# design.net
KiCad netlist of a schematic drawn in Altium Designer
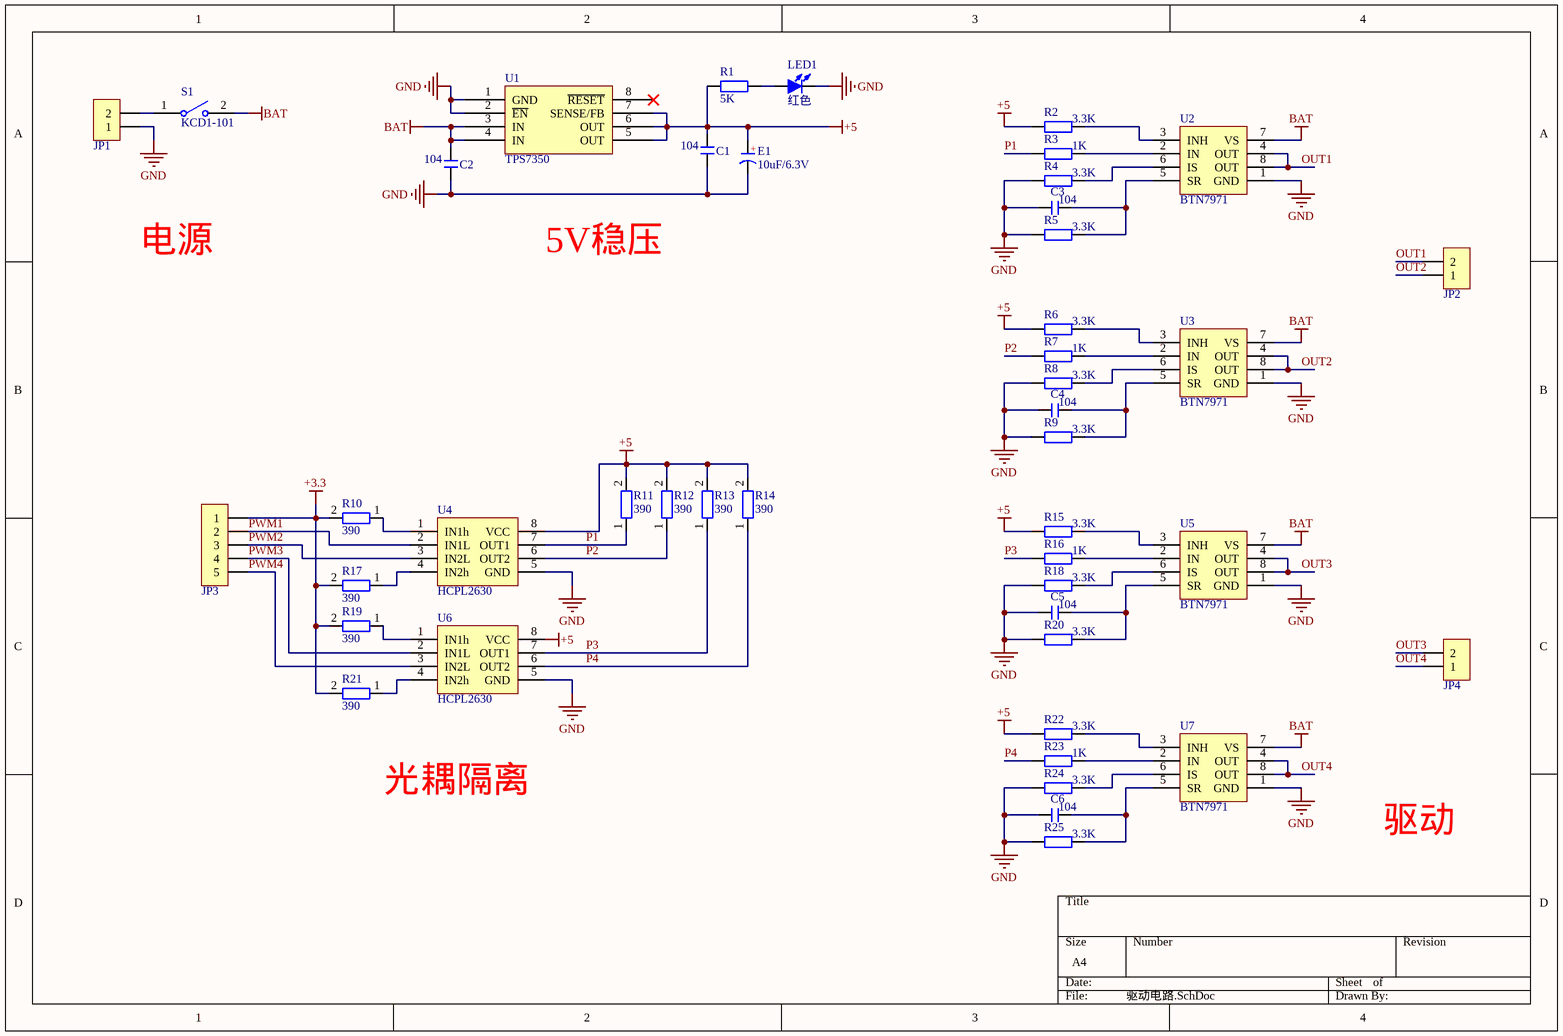
[diagram p0: 驱动电路.SchDoc]

(export (version "E")
  (design (tool "Eeschema 10.0.6"))
  (components
    (comp (ref "C1")
      (value "104")
      (footprint "C 0805_M")
      (description "无极性贴片电容")
      (fields (field (name "版权归属") "源创客"))
      (libsource (lib "3.1   - 电阻-电容-电感") (part "C"))
    )
    (comp (ref "C2")
      (value "104")
      (footprint "C 0805_M")
      (description "无极性贴片电容")
      (fields (field (name "版权归属") "源创客"))
      (libsource (lib "3.1   - 电阻-电容-电感") (part "C"))
    )
    (comp (ref "C3")
      (value "104")
      (footprint "C 0805_M")
      (description "无极性贴片电容")
      (fields (field (name "版权归属") "源创客"))
      (libsource (lib "3.1   - 电阻-电容-电感") (part "C"))
    )
    (comp (ref "C4")
      (value "104")
      (footprint "C 0805_M")
      (description "无极性贴片电容")
      (fields (field (name "版权归属") "源创客"))
      (libsource (lib "3.1   - 电阻-电容-电感") (part "C"))
    )
    (comp (ref "C5")
      (value "104")
      (footprint "C 0805_M")
      (description "无极性贴片电容")
      (fields (field (name "版权归属") "源创客"))
      (libsource (lib "3.1   - 电阻-电容-电感") (part "C"))
    )
    (comp (ref "C6")
      (value "104")
      (footprint "C 0805_M")
      (description "无极性贴片电容")
      (fields (field (name "版权归属") "源创客"))
      (libsource (lib "3.1   - 电阻-电容-电感") (part "C"))
    )
    (comp (ref "E1")
      (value "10uF/6.3V")
      (footprint "CD A(3216)")
      (description "贴片钽电容")
      (fields (field (name "版权归属") "源创客"))
      (libsource (lib "3.1   - 电阻-电容-电感") (part "C-CD"))
    )
    (comp (ref "JP1")
      (value "HDR-1X2")
      (footprint "KF128-5.08-2P")
      (description "2P接插件")
      (fields (field (name "版权归属") "源创客"))
      (libsource (lib "") (part "Header 2_1"))
    )
    (comp (ref "JP2")
      (value "HDR-1X2")
      (footprint "KF128-5.08-2P")
      (description "2P接插件")
      (fields (field (name "版权归属") "源创客"))
      (libsource (lib "4.10 - 接插件-脚距5.08") (part "Header 2"))
    )
    (comp (ref "JP3")
      (value "HDR-1X5")
      (footprint "XH2.54-LI-5P")
      (description "5P接插件")
      (fields (field (name "版权归属") "源创客"))
      (libsource (lib "4.5   - 接插件-脚距2.54") (part "Header 5"))
    )
    (comp (ref "JP4")
      (value "HDR-1X2")
      (footprint "KF128-5.08-2P")
      (description "2P接插件")
      (fields (field (name "版权归属") "源创客"))
      (libsource (lib "4.10 - 接插件-脚距5.08") (part "Header 2"))
    )
    (comp (ref "LED1")
      (value "红色")
      (footprint "LED 0805R")
      (description "贴片LED")
      (fields (field (name "版权归属") "源创客"))
      (libsource (lib "9.1   - LED") (part "LED-SMD"))
    )
    (comp (ref "R1")
      (value "5K")
      (footprint "R 0805-HP_M")
      (description "精密贴片电阻")
      (fields (field (name "版权归属") "源创客"))
      (libsource (lib "3.1   - 电阻-电容-电感") (part "R-Precision"))
    )
    (comp (ref "R2")
      (value "3.3K")
      (footprint "R 0805-HP_M")
      (description "精密贴片电阻")
      (fields (field (name "版权归属") "源创客"))
      (libsource (lib "3.1   - 电阻-电容-电感") (part "R-Precision"))
    )
    (comp (ref "R3")
      (value "1K")
      (footprint "R 0805-HP_M")
      (description "精密贴片电阻")
      (fields (field (name "版权归属") "源创客"))
      (libsource (lib "3.1   - 电阻-电容-电感") (part "R-Precision"))
    )
    (comp (ref "R4")
      (value "3.3K")
      (footprint "R 0805-HP_M")
      (description "精密贴片电阻")
      (fields (field (name "版权归属") "源创客"))
      (libsource (lib "3.1   - 电阻-电容-电感") (part "R-Precision"))
    )
    (comp (ref "R5")
      (value "3.3K")
      (footprint "R 0805-HP_M")
      (description "精密贴片电阻")
      (fields (field (name "版权归属") "源创客"))
      (libsource (lib "3.1   - 电阻-电容-电感") (part "R-Precision"))
    )
    (comp (ref "R6")
      (value "3.3K")
      (footprint "R 0805-HP_M")
      (description "精密贴片电阻")
      (fields (field (name "版权归属") "源创客"))
      (libsource (lib "3.1   - 电阻-电容-电感") (part "R-Precision"))
    )
    (comp (ref "R7")
      (value "1K")
      (footprint "R 0805-HP_M")
      (description "精密贴片电阻")
      (fields (field (name "版权归属") "源创客"))
      (libsource (lib "3.1   - 电阻-电容-电感") (part "R-Precision"))
    )
    (comp (ref "R8")
      (value "3.3K")
      (footprint "R 0805-HP_M")
      (description "精密贴片电阻")
      (fields (field (name "版权归属") "源创客"))
      (libsource (lib "3.1   - 电阻-电容-电感") (part "R-Precision"))
    )
    (comp (ref "R9")
      (value "3.3K")
      (footprint "R 0805-HP_M")
      (description "精密贴片电阻")
      (fields (field (name "版权归属") "源创客"))
      (libsource (lib "3.1   - 电阻-电容-电感") (part "R-Precision"))
    )
    (comp (ref "R10")
      (value "390")
      (footprint "R 2512_M")
      (description "贴片电阻")
      (fields (field (name "版权归属") "源创客"))
      (libsource (lib "3.1   - 电阻-电容-电感") (part "R"))
    )
    (comp (ref "R11")
      (value "390")
      (footprint "R 2512_M")
      (description "贴片电阻")
      (fields (field (name "版权归属") "源创客"))
      (libsource (lib "3.1   - 电阻-电容-电感") (part "R"))
    )
    (comp (ref "R12")
      (value "390")
      (footprint "R 2512_M")
      (description "贴片电阻")
      (fields (field (name "版权归属") "源创客"))
      (libsource (lib "3.1   - 电阻-电容-电感") (part "R"))
    )
    (comp (ref "R13")
      (value "390")
      (footprint "R 2512_M")
      (description "贴片电阻")
      (fields (field (name "版权归属") "源创客"))
      (libsource (lib "3.1   - 电阻-电容-电感") (part "R"))
    )
    (comp (ref "R14")
      (value "390")
      (footprint "R 2512_M")
      (description "贴片电阻")
      (fields (field (name "版权归属") "源创客"))
      (libsource (lib "3.1   - 电阻-电容-电感") (part "R"))
    )
    (comp (ref "R15")
      (value "3.3K")
      (footprint "R 0805-HP_M")
      (description "精密贴片电阻")
      (fields (field (name "版权归属") "源创客"))
      (libsource (lib "3.1   - 电阻-电容-电感") (part "R-Precision"))
    )
    (comp (ref "R16")
      (value "1K")
      (footprint "R 0805-HP_M")
      (description "精密贴片电阻")
      (fields (field (name "版权归属") "源创客"))
      (libsource (lib "3.1   - 电阻-电容-电感") (part "R-Precision"))
    )
    (comp (ref "R17")
      (value "390")
      (footprint "R 2512_M")
      (description "贴片电阻")
      (fields (field (name "版权归属") "源创客"))
      (libsource (lib "3.1   - 电阻-电容-电感") (part "R"))
    )
    (comp (ref "R18")
      (value "3.3K")
      (footprint "R 0805-HP_M")
      (description "精密贴片电阻")
      (fields (field (name "版权归属") "源创客"))
      (libsource (lib "3.1   - 电阻-电容-电感") (part "R-Precision"))
    )
    (comp (ref "R19")
      (value "390")
      (footprint "R 2512_M")
      (description "贴片电阻")
      (fields (field (name "版权归属") "源创客"))
      (libsource (lib "3.1   - 电阻-电容-电感") (part "R"))
    )
    (comp (ref "R20")
      (value "3.3K")
      (footprint "R 0805-HP_M")
      (description "精密贴片电阻")
      (fields (field (name "版权归属") "源创客"))
      (libsource (lib "3.1   - 电阻-电容-电感") (part "R-Precision"))
    )
    (comp (ref "R21")
      (value "390")
      (footprint "R 2512_M")
      (description "贴片电阻")
      (fields (field (name "版权归属") "源创客"))
      (libsource (lib "3.1   - 电阻-电容-电感") (part "R"))
    )
    (comp (ref "R22")
      (value "3.3K")
      (footprint "R 0805-HP_M")
      (description "精密贴片电阻")
      (fields (field (name "版权归属") "源创客"))
      (libsource (lib "3.1   - 电阻-电容-电感") (part "R-Precision"))
    )
    (comp (ref "R23")
      (value "1K")
      (footprint "R 0805-HP_M")
      (description "精密贴片电阻")
      (fields (field (name "版权归属") "源创客"))
      (libsource (lib "3.1   - 电阻-电容-电感") (part "R-Precision"))
    )
    (comp (ref "R24")
      (value "3.3K")
      (footprint "R 0805-HP_M")
      (description "精密贴片电阻")
      (fields (field (name "版权归属") "源创客"))
      (libsource (lib "3.1   - 电阻-电容-电感") (part "R-Precision"))
    )
    (comp (ref "R25")
      (value "3.3K")
      (footprint "R 0805-HP_M")
      (description "精密贴片电阻")
      (fields (field (name "版权归属") "源创客"))
      (libsource (lib "3.1   - 电阻-电容-电感") (part "R-Precision"))
    )
    (comp (ref "S1")
      (value "KCD1-101")
      (footprint "KCD1-101")
      (description "1路单刀船型开关")
      (fields (field (name "版权归属") "源创客"))
      (libsource (lib "5.1   - 按键-开关") (part "KCD1-101"))
    )
    (comp (ref "U1")
      (value "TPS7350")
      (footprint "SOP8")
      (description "稳压")
      (libsource (lib "tps7350") (part "TPS7350"))
    )
    (comp (ref "U2")
      (value "BTN7971")
      (footprint "DPAK127P1615X127-8N")
      (libsource (lib "驱动电路1-0") (part "BTN7971"))
    )
    (comp (ref "U3")
      (value "BTN7971")
      (footprint "DPAK127P1615X127-8N")
      (libsource (lib "驱动电路1-0") (part "BTN7971"))
    )
    (comp (ref "U4") (value "HCPL2630") (footprint "SOP8") (libsource (lib "驱动电路1-0") (part "HCPL2630")))
    (comp (ref "U5")
      (value "BTN7971")
      (footprint "DPAK127P1615X127-8N")
      (libsource (lib "驱动电路1-0") (part "BTN7971"))
    )
    (comp (ref "U6") (value "HCPL2630") (footprint "SOP8") (libsource (lib "驱动电路1-0") (part "HCPL2630")))
    (comp (ref "U7")
      (value "BTN7971")
      (footprint "DPAK127P1615X127-8N")
      (libsource (lib "驱动电路1-0") (part "BTN7971"))
    )
  )
  (nets
    (net (code "1") (name "+3.3") (class "Default")
      (node (ref "JP3") (pin "1") (pinfunction "1_1") (pintype "passive"))
      (node (ref "R10") (pin "2") (pinfunction "2_2") (pintype "passive"))
      (node (ref "R17") (pin "2") (pinfunction "2_2") (pintype "passive"))
      (node (ref "R19") (pin "2") (pinfunction "2_2") (pintype "passive"))
      (node (ref "R21") (pin "2") (pinfunction "2_2") (pintype "passive"))
    )
    (net (code "2") (name "+5") (class "Default")
      (node (ref "C1") (pin "2") (pinfunction "2_2") (pintype "passive"))
      (node (ref "E1") (pin "1") (pinfunction "A_1") (pintype "passive"))
      (node (ref "R1") (pin "1") (pinfunction "1_1") (pintype "passive"))
      (node (ref "R11") (pin "2") (pinfunction "2_2") (pintype "passive"))
      (node (ref "R12") (pin "2") (pinfunction "2_2") (pintype "passive"))
      (node (ref "R13") (pin "2") (pinfunction "2_2") (pintype "passive"))
      (node (ref "R14") (pin "2") (pinfunction "2_2") (pintype "passive"))
      (node (ref "R15") (pin "1") (pinfunction "1_1") (pintype "passive"))
      (node (ref "R2") (pin "1") (pinfunction "1_1") (pintype "passive"))
      (node (ref "R22") (pin "1") (pinfunction "1_1") (pintype "passive"))
      (node (ref "R6") (pin "1") (pinfunction "1_1") (pintype "passive"))
      (node (ref "U1") (pin "5") (pinfunction "OUT_5") (pintype "passive"))
      (node (ref "U1") (pin "6") (pinfunction "OUT_6") (pintype "passive"))
      (node (ref "U1") (pin "7") (pinfunction "SENSE/FB_7") (pintype "passive"))
      (node (ref "U4") (pin "8") (pinfunction "VCC_8") (pintype "passive"))
      (node (ref "U6") (pin "8") (pinfunction "VCC_8") (pintype "passive"))
    )
    (net (code "3") (name "/OUT1") (class "Default")
      (node (ref "JP2") (pin "2") (pinfunction "2_2") (pintype "passive"))
      (node (ref "U2") (pin "4") (pinfunction "OUT_4") (pintype "passive"))
      (node (ref "U2") (pin "8") (pinfunction "OUT_8") (pintype "passive"))
    )
    (net (code "4") (name "/OUT2") (class "Default")
      (node (ref "JP2") (pin "1") (pinfunction "1_1") (pintype "passive"))
      (node (ref "U3") (pin "4") (pinfunction "OUT_4") (pintype "passive"))
      (node (ref "U3") (pin "8") (pinfunction "OUT_8") (pintype "passive"))
    )
    (net (code "5") (name "/OUT3") (class "Default")
      (node (ref "JP4") (pin "2") (pinfunction "2_2") (pintype "passive"))
      (node (ref "U5") (pin "4") (pinfunction "OUT_4") (pintype "passive"))
      (node (ref "U5") (pin "8") (pinfunction "OUT_8") (pintype "passive"))
    )
    (net (code "6") (name "/OUT4") (class "Default")
      (node (ref "JP4") (pin "1") (pinfunction "1_1") (pintype "passive"))
      (node (ref "U7") (pin "4") (pinfunction "OUT_4") (pintype "passive"))
      (node (ref "U7") (pin "8") (pinfunction "OUT_8") (pintype "passive"))
    )
    (net (code "7") (name "/P1") (class "Default")
      (node (ref "R11") (pin "1") (pinfunction "1_1") (pintype "passive"))
      (node (ref "R3") (pin "1") (pinfunction "1_1") (pintype "passive"))
      (node (ref "U4") (pin "7") (pinfunction "OUT1_7") (pintype "passive"))
    )
    (net (code "8") (name "/P2") (class "Default")
      (node (ref "R12") (pin "1") (pinfunction "1_1") (pintype "passive"))
      (node (ref "R7") (pin "1") (pinfunction "1_1") (pintype "passive"))
      (node (ref "U4") (pin "6") (pinfunction "OUT2_6") (pintype "passive"))
    )
    (net (code "9") (name "/P3") (class "Default")
      (node (ref "R13") (pin "1") (pinfunction "1_1") (pintype "passive"))
      (node (ref "R16") (pin "1") (pinfunction "1_1") (pintype "passive"))
      (node (ref "U6") (pin "7") (pinfunction "OUT1_7") (pintype "passive"))
    )
    (net (code "10") (name "/P4") (class "Default")
      (node (ref "R14") (pin "1") (pinfunction "1_1") (pintype "passive"))
      (node (ref "R23") (pin "1") (pinfunction "1_1") (pintype "passive"))
      (node (ref "U6") (pin "6") (pinfunction "OUT2_6") (pintype "passive"))
    )
    (net (code "11") (name "/PWM1") (class "Default")
      (node (ref "JP3") (pin "2") (pinfunction "2_2") (pintype "passive"))
      (node (ref "U4") (pin "2") (pinfunction "IN1L_2") (pintype "passive"))
    )
    (net (code "12") (name "/PWM2") (class "Default")
      (node (ref "JP3") (pin "3") (pinfunction "3_3") (pintype "passive"))
      (node (ref "U4") (pin "3") (pinfunction "IN2L_3") (pintype "passive"))
    )
    (net (code "13") (name "/PWM3") (class "Default")
      (node (ref "JP3") (pin "4") (pinfunction "4_4") (pintype "passive"))
      (node (ref "U6") (pin "2") (pinfunction "IN1L_2") (pintype "passive"))
    )
    (net (code "14") (name "/PWM4") (class "Default")
      (node (ref "JP3") (pin "5") (pinfunction "5_5") (pintype "passive"))
      (node (ref "U6") (pin "3") (pinfunction "IN2L_3") (pintype "passive"))
    )
    (net (code "15") (name "BAT") (class "Default")
      (node (ref "C2") (pin "2") (pinfunction "2_2") (pintype "passive"))
      (node (ref "S1") (pin "2") (pinfunction "2_2") (pintype "passive"))
      (node (ref "U1") (pin "3") (pinfunction "IN_3") (pintype "passive"))
      (node (ref "U1") (pin "4") (pinfunction "IN_4") (pintype "passive"))
      (node (ref "U2") (pin "7") (pinfunction "VS_7") (pintype "passive"))
      (node (ref "U3") (pin "7") (pinfunction "VS_7") (pintype "passive"))
      (node (ref "U5") (pin "7") (pinfunction "VS_7") (pintype "passive"))
      (node (ref "U7") (pin "7") (pinfunction "VS_7") (pintype "passive"))
    )
    (net (code "16") (name "GND") (class "Default")
      (node (ref "C1") (pin "1") (pinfunction "1_1") (pintype "passive"))
      (node (ref "C2") (pin "1") (pinfunction "1_1") (pintype "passive"))
      (node (ref "C3") (pin "2") (pinfunction "2_2") (pintype "passive"))
      (node (ref "C4") (pin "2") (pinfunction "2_2") (pintype "passive"))
      (node (ref "C5") (pin "2") (pinfunction "2_2") (pintype "passive"))
      (node (ref "C6") (pin "2") (pinfunction "2_2") (pintype "passive"))
      (node (ref "E1") (pin "2") (pinfunction "K_2") (pintype "passive"))
      (node (ref "JP1") (pin "1") (pinfunction "1_1") (pintype "passive"))
      (node (ref "LED1") (pin "2") (pinfunction "K_2") (pintype "passive"))
      (node (ref "R18") (pin "1") (pinfunction "1_1") (pintype "passive"))
      (node (ref "R20") (pin "1") (pinfunction "1_1") (pintype "passive"))
      (node (ref "R24") (pin "1") (pinfunction "1_1") (pintype "passive"))
      (node (ref "R25") (pin "1") (pinfunction "1_1") (pintype "passive"))
      (node (ref "R4") (pin "1") (pinfunction "1_1") (pintype "passive"))
      (node (ref "R5") (pin "1") (pinfunction "1_1") (pintype "passive"))
      (node (ref "R8") (pin "1") (pinfunction "1_1") (pintype "passive"))
      (node (ref "R9") (pin "1") (pinfunction "1_1") (pintype "passive"))
      (node (ref "U1") (pin "1") (pinfunction "GND_1") (pintype "passive"))
      (node (ref "U1") (pin "2") (pinfunction "~{EN}_2") (pintype "passive"))
      (node (ref "U2") (pin "1") (pinfunction "GND_1") (pintype "passive"))
      (node (ref "U3") (pin "1") (pinfunction "GND_1") (pintype "passive"))
      (node (ref "U4") (pin "5") (pinfunction "GND_5") (pintype "passive"))
      (node (ref "U5") (pin "1") (pinfunction "GND_1") (pintype "passive"))
      (node (ref "U6") (pin "5") (pinfunction "GND_5") (pintype "passive"))
      (node (ref "U7") (pin "1") (pinfunction "GND_1") (pintype "passive"))
    )
    (net (code "17") (name "Net-(JP1-Pad2)") (class "Default")
      (node (ref "JP1") (pin "2") (pinfunction "2_2") (pintype "passive"))
      (node (ref "S1") (pin "1") (pinfunction "1_1") (pintype "passive"))
    )
    (net (code "18") (name "Net-(LED1-A)") (class "Default")
      (node (ref "LED1") (pin "1") (pinfunction "A_1") (pintype "passive"))
      (node (ref "R1") (pin "2") (pinfunction "2_2") (pintype "passive"))
    )
    (net (code "19") (name "Net-(U2-IN)") (class "Default")
      (node (ref "R3") (pin "2") (pinfunction "2_2") (pintype "passive"))
      (node (ref "U2") (pin "2") (pinfunction "IN_2") (pintype "passive"))
    )
    (net (code "20") (name "Net-(U2-INH)") (class "Default")
      (node (ref "R2") (pin "2") (pinfunction "2_2") (pintype "passive"))
      (node (ref "U2") (pin "3") (pinfunction "INH_3") (pintype "passive"))
    )
    (net (code "21") (name "Net-(U2-IS)") (class "Default")
      (node (ref "R4") (pin "2") (pinfunction "2_2") (pintype "passive"))
      (node (ref "U2") (pin "6") (pinfunction "IS_6") (pintype "passive"))
    )
    (net (code "22") (name "Net-(U2-SR)") (class "Default")
      (node (ref "C3") (pin "1") (pinfunction "1_1") (pintype "passive"))
      (node (ref "R5") (pin "2") (pinfunction "2_2") (pintype "passive"))
      (node (ref "U2") (pin "5") (pinfunction "SR_5") (pintype "passive"))
    )
    (net (code "23") (name "Net-(U3-IN)") (class "Default")
      (node (ref "R7") (pin "2") (pinfunction "2_2") (pintype "passive"))
      (node (ref "U3") (pin "2") (pinfunction "IN_2") (pintype "passive"))
    )
    (net (code "24") (name "Net-(U3-INH)") (class "Default")
      (node (ref "R6") (pin "2") (pinfunction "2_2") (pintype "passive"))
      (node (ref "U3") (pin "3") (pinfunction "INH_3") (pintype "passive"))
    )
    (net (code "25") (name "Net-(U3-IS)") (class "Default")
      (node (ref "R8") (pin "2") (pinfunction "2_2") (pintype "passive"))
      (node (ref "U3") (pin "6") (pinfunction "IS_6") (pintype "passive"))
    )
    (net (code "26") (name "Net-(U3-SR)") (class "Default")
      (node (ref "C4") (pin "1") (pinfunction "1_1") (pintype "passive"))
      (node (ref "R9") (pin "2") (pinfunction "2_2") (pintype "passive"))
      (node (ref "U3") (pin "5") (pinfunction "SR_5") (pintype "passive"))
    )
    (net (code "27") (name "Net-(U4-IN1h)") (class "Default")
      (node (ref "R10") (pin "1") (pinfunction "1_1") (pintype "passive"))
      (node (ref "U4") (pin "1") (pinfunction "IN1h_1") (pintype "passive"))
    )
    (net (code "28") (name "Net-(U4-IN2h)") (class "Default")
      (node (ref "R17") (pin "1") (pinfunction "1_1") (pintype "passive"))
      (node (ref "U4") (pin "4") (pinfunction "IN2h_4") (pintype "passive"))
    )
    (net (code "29") (name "Net-(U5-IN)") (class "Default")
      (node (ref "R16") (pin "2") (pinfunction "2_2") (pintype "passive"))
      (node (ref "U5") (pin "2") (pinfunction "IN_2") (pintype "passive"))
    )
    (net (code "30") (name "Net-(U5-INH)") (class "Default")
      (node (ref "R15") (pin "2") (pinfunction "2_2") (pintype "passive"))
      (node (ref "U5") (pin "3") (pinfunction "INH_3") (pintype "passive"))
    )
    (net (code "31") (name "Net-(U5-IS)") (class "Default")
      (node (ref "R18") (pin "2") (pinfunction "2_2") (pintype "passive"))
      (node (ref "U5") (pin "6") (pinfunction "IS_6") (pintype "passive"))
    )
    (net (code "32") (name "Net-(U5-SR)") (class "Default")
      (node (ref "C5") (pin "1") (pinfunction "1_1") (pintype "passive"))
      (node (ref "R20") (pin "2") (pinfunction "2_2") (pintype "passive"))
      (node (ref "U5") (pin "5") (pinfunction "SR_5") (pintype "passive"))
    )
    (net (code "33") (name "Net-(U6-IN1h)") (class "Default")
      (node (ref "R19") (pin "1") (pinfunction "1_1") (pintype "passive"))
      (node (ref "U6") (pin "1") (pinfunction "IN1h_1") (pintype "passive"))
    )
    (net (code "34") (name "Net-(U6-IN2h)") (class "Default")
      (node (ref "R21") (pin "1") (pinfunction "1_1") (pintype "passive"))
      (node (ref "U6") (pin "4") (pinfunction "IN2h_4") (pintype "passive"))
    )
    (net (code "35") (name "Net-(U7-IN)") (class "Default")
      (node (ref "R23") (pin "2") (pinfunction "2_2") (pintype "passive"))
      (node (ref "U7") (pin "2") (pinfunction "IN_2") (pintype "passive"))
    )
    (net (code "36") (name "Net-(U7-INH)") (class "Default")
      (node (ref "R22") (pin "2") (pinfunction "2_2") (pintype "passive"))
      (node (ref "U7") (pin "3") (pinfunction "INH_3") (pintype "passive"))
    )
    (net (code "37") (name "Net-(U7-IS)") (class "Default")
      (node (ref "R24") (pin "2") (pinfunction "2_2") (pintype "passive"))
      (node (ref "U7") (pin "6") (pinfunction "IS_6") (pintype "passive"))
    )
    (net (code "38") (name "Net-(U7-SR)") (class "Default")
      (node (ref "C6") (pin "1") (pinfunction "1_1") (pintype "passive"))
      (node (ref "R25") (pin "2") (pinfunction "2_2") (pintype "passive"))
      (node (ref "U7") (pin "5") (pinfunction "SR_5") (pintype "passive"))
    )
    (net (code "39") (name "unconnected-(U1-~{RESET}-Pad8)") (class "Default")
      (node (ref "U1") (pin "8") (pinfunction "~{RESET}_8") (pintype "passive+no_connect"))
    )
  )
)
